# 31_Pwr_In.net
KiCad netlist of a schematic drawn in Altium Designer
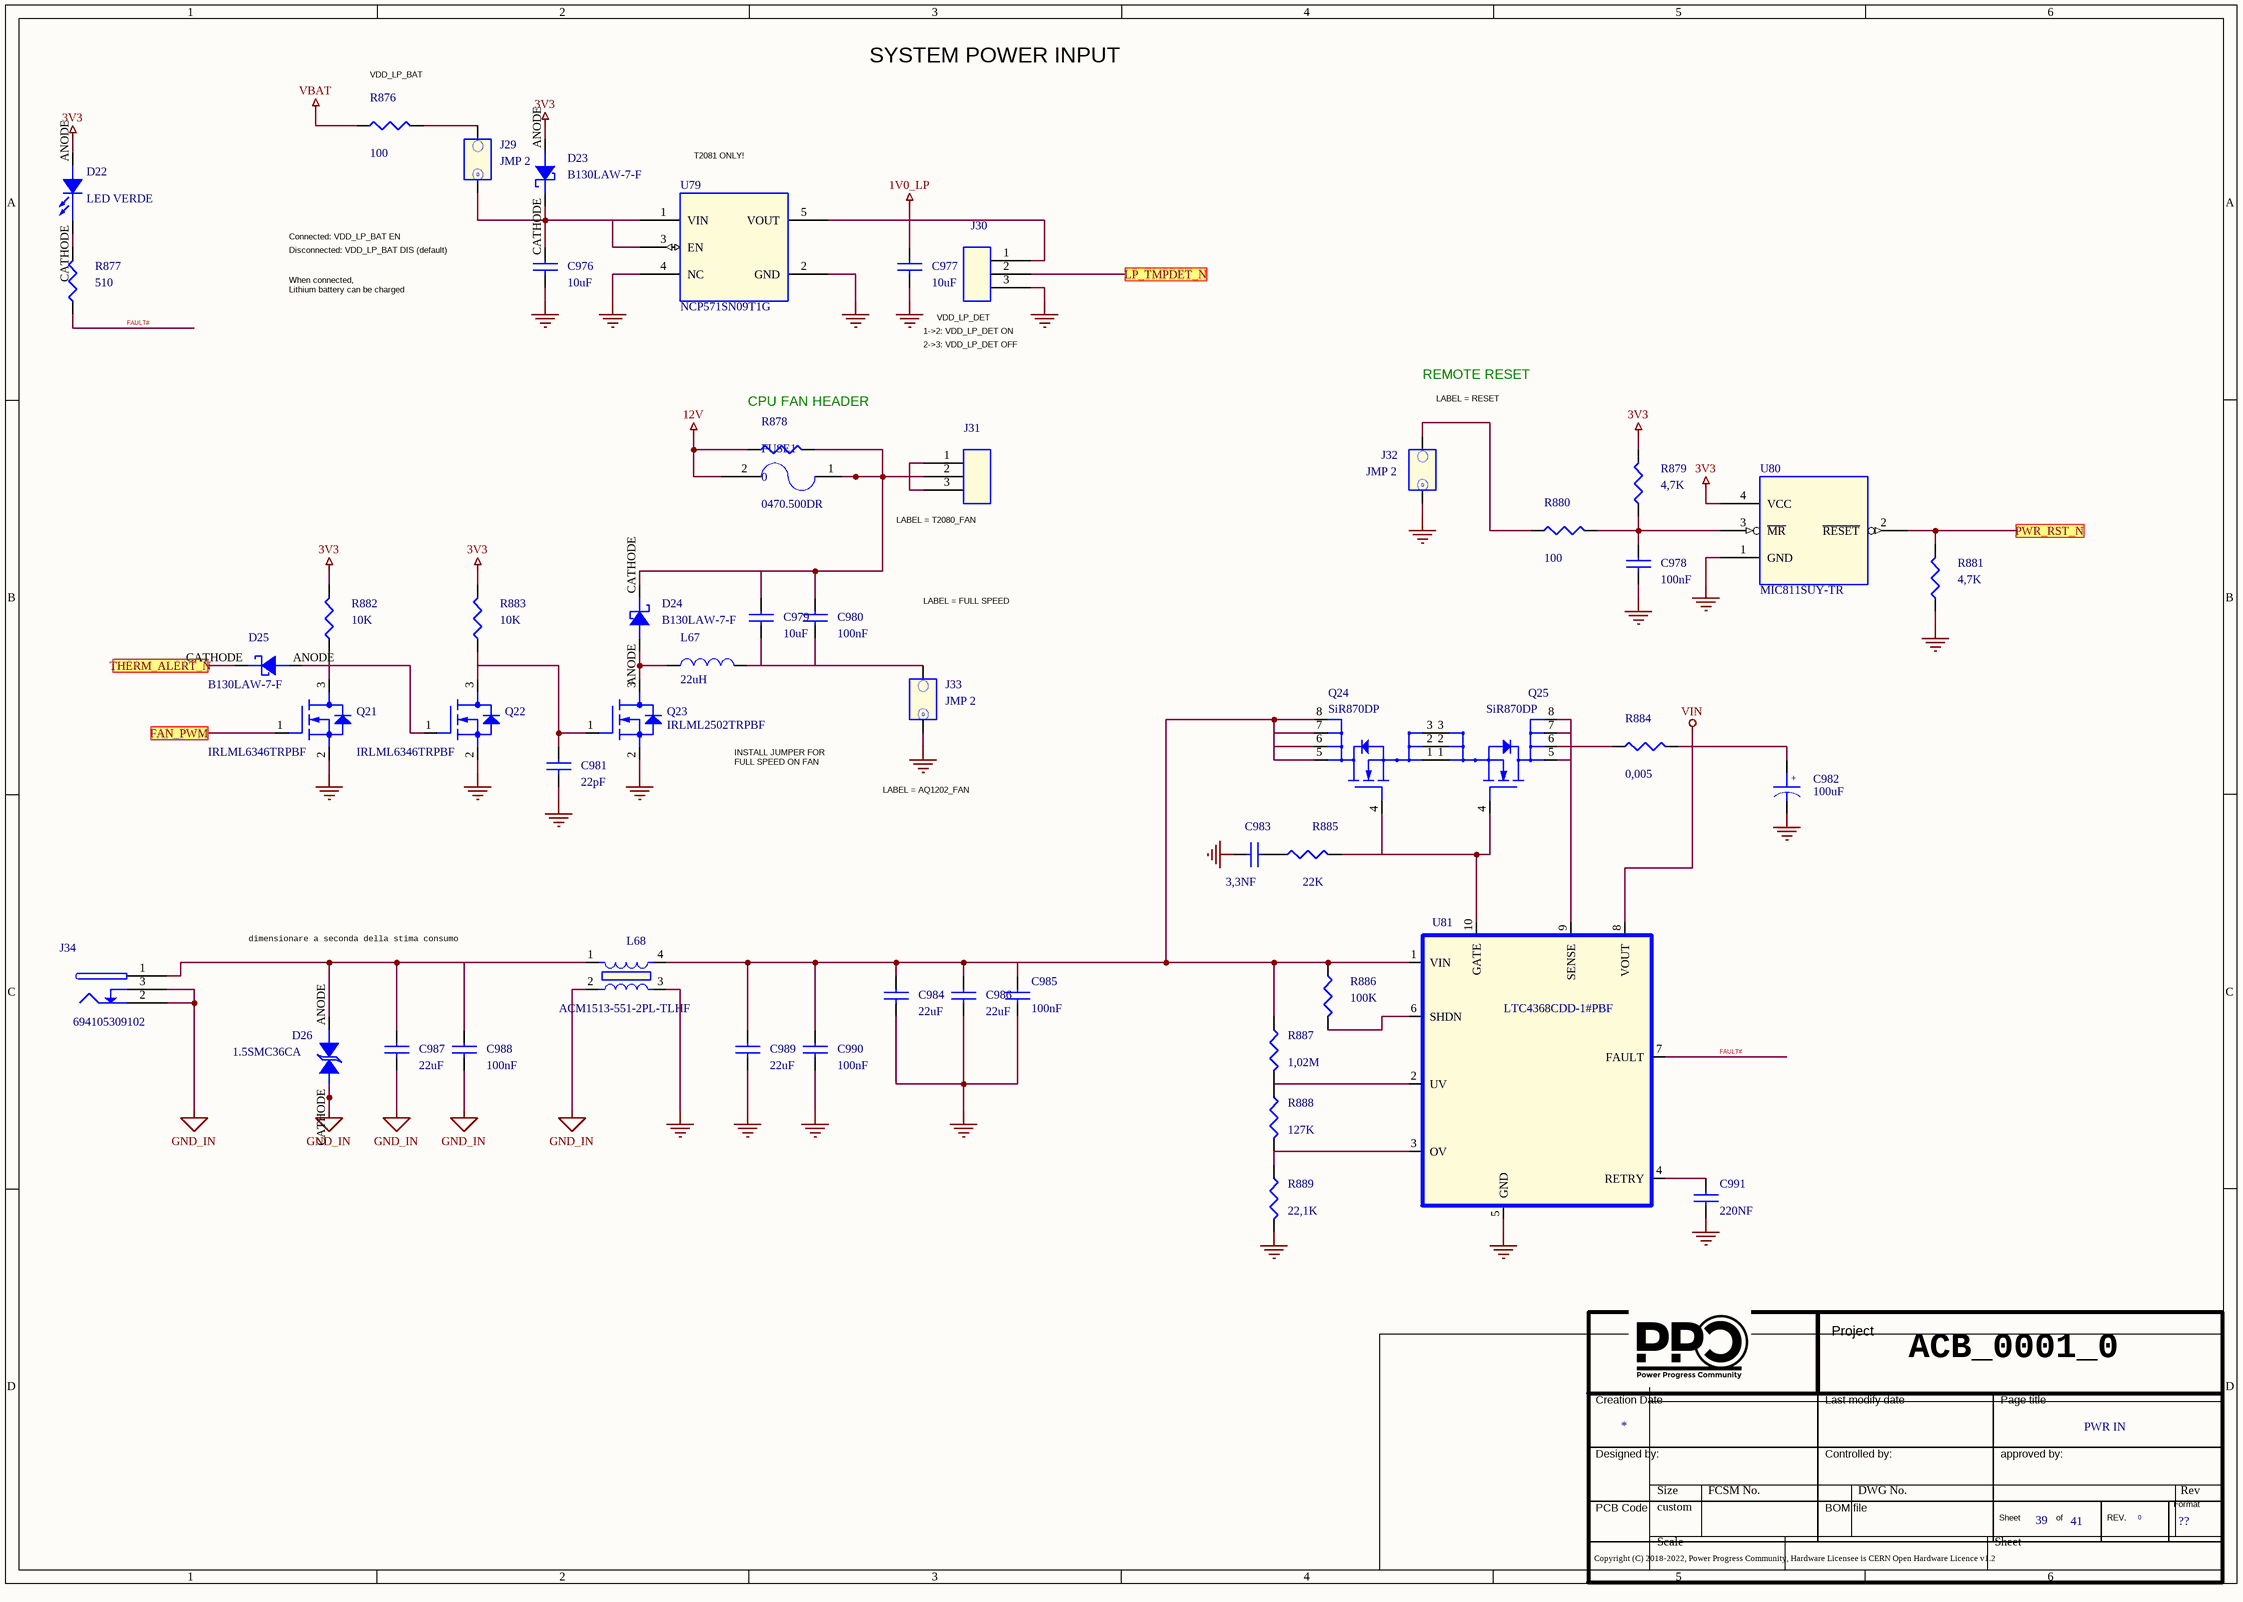
[diagram p0: 31 Pwr In.SchDoc]

(export (version "E")
  (design (tool "Eeschema 10.0.6"))
  (components
    (comp (ref "C976")
      (value "10uF")
      (footprint "SMD_0603")
      (description "COND.CER.10uF 0603 25V SMD")
      (fields (field (name "PART NUMBER") "PASSIVE_124"))
      (libsource (lib "*") (part "CAP NP_Dup3"))
    )
    (comp (ref "C977")
      (value "10uF")
      (footprint "SMD_0603")
      (description "COND.CER.10uF 0603 25V SMD")
      (fields (field (name "PART NUMBER") "PASSIVE_124"))
      (libsource (lib "*") (part "CAP NP_Dup3"))
    )
    (comp (ref "C978")
      (value "100nF")
      (footprint "SMD_0402")
      (description "COND.CER. 100NF 50V 0402 X7R SMD")
      (fields (field (name "PART NUMBER") "PASSIVE_24"))
      (libsource (lib "*") (part "CAP NP_Dup3"))
    )
    (comp (ref "C979")
      (value "10uF")
      (footprint "SMD_0603")
      (description "COND.CER.10uF 0603 25V SMD")
      (fields (field (name "PART NUMBER") "PASSIVE_124"))
      (libsource (lib "*") (part "CAP NP_Dup3"))
    )
    (comp (ref "C980")
      (value "100nF")
      (footprint "SMD_0402")
      (description "COND.CER. 100NF 50V 0402 X7R SMD")
      (fields (field (name "PART NUMBER") "PASSIVE_24"))
      (libsource (lib "*") (part "CAP NP_Dup3"))
    )
    (comp (ref "C981")
      (value "22pF")
      (footprint "SMD_0402")
      (description "COND.CER. 22PF 50V 0402 NPO 5% SMD")
      (fields (field (name "PART NUMBER") "PASSIVE_65"))
      (libsource (lib "*") (part "CAP NP_Dup3"))
    )
    (comp (ref "C982")
      (value "100uF")
      (footprint "SMD_8.3X8.3")
      (description "CAP ALUM 100UF 35V 20% SMD")
      (fields (field (name "PART NUMBER") "PASSIVE_307"))
      (libsource (lib "*") (part "CAP POL_Dup2"))
    )
    (comp (ref "C983")
      (value "3,3NF")
      (footprint "SMD_0402")
      (description "COND.CER. 3,3NF 50V 0402 X7R SMD")
      (fields (field (name "PART NUMBER") "PASSIVE_69"))
      (libsource (lib "*") (part "CAP NP_Dup10"))
    )
    (comp (ref "C984")
      (value "22uF")
      (footprint "SMD_0805")
      (description "22UF 35V 20% 0805")
      (fields (field (name "PART NUMBER") "PASSIVE_224"))
      (libsource (lib "*") (part "CAP NP_Dup3"))
    )
    (comp (ref "C985")
      (value "100nF")
      (footprint "SMD_0603")
      (description "COND.CER.100NF 50V 0603 X7R SMD")
      (fields (field (name "PART NUMBER") "PASSIVE_118"))
      (libsource (lib "*") (part "CAP NP_Dup10"))
    )
    (comp (ref "C986")
      (value "22uF")
      (footprint "SMD_0805")
      (description "22UF 35V 20% 0805")
      (fields (field (name "PART NUMBER") "PASSIVE_224"))
      (libsource (lib "*") (part "CAP NP_Dup3"))
    )
    (comp (ref "C987")
      (value "22uF")
      (footprint "SMD_0805")
      (description "22UF 35V 20% 0805")
      (fields (field (name "PART NUMBER") "PASSIVE_224"))
      (libsource (lib "*") (part "CAP NP_Dup3"))
    )
    (comp (ref "C988")
      (value "100nF")
      (footprint "SMD_0603")
      (description "COND.CER.100NF 50V 0603 X7R SMD")
      (fields (field (name "LNK_PART") "C0603X90") (field (name "PART NUMBER") "PASSIVE_118"))
      (libsource (lib "*") (part "CAP NP_Dup10"))
    )
    (comp (ref "C989")
      (value "22uF")
      (footprint "SMD_0805")
      (description "22UF 35V 20% 0805")
      (fields (field (name "PART NUMBER") "PASSIVE_224"))
      (libsource (lib "*") (part "CAP NP_Dup3"))
    )
    (comp (ref "C990")
      (value "100nF")
      (footprint "SMD_0603")
      (description "COND.CER.100NF 50V 0603 X7R SMD")
      (fields (field (name "LNK_PART") "C0603X90") (field (name "PART NUMBER") "PASSIVE_118"))
      (libsource (lib "*") (part "CAP NP_Dup10"))
    )
    (comp (ref "C991")
      (value "220NF")
      (footprint "SMD_0402")
      (description "COND.CER. 220NF 10V 0402 X5R SMD")
      (fields (field (name "PART NUMBER") "PASSIVE_60"))
      (libsource (lib "*") (part "CAP NP_Dup10"))
    )
    (comp (ref "D22")
      (value "LED VERDE")
      (footprint "led_0603")
      (description "LED CHIPLED VERDE 40mcd 570nm")
      (fields (field (name "PART NUMBER") "DISCRETE_31"))
      (libsource (lib "*") (part "LED_1"))
    )
    (comp (ref "D23")
      (value "B130LAW-7-F")
      (footprint "SOD-123")
      (description "DIODE SCHOTTKY 30V 1A SOD123")
      (fields (field (name "PART NUMBER") "DISCRETE_74"))
      (libsource (lib "*") (part "diode_schottky"))
    )
    (comp (ref "D24")
      (value "B130LAW-7-F")
      (footprint "SOD-123")
      (description "DIODE SCHOTTKY 30V 1A SOD123")
      (fields (field (name "PART NUMBER") "DISCRETE_74"))
      (libsource (lib "*") (part "diode_schottky"))
    )
    (comp (ref "D25")
      (value "B130LAW-7-F")
      (footprint "SOD-123")
      (description "DIODE SCHOTTKY 30V 1A SOD123")
      (fields (field (name "PART NUMBER") "DISCRETE_74"))
      (libsource (lib "*") (part "diode_schottky"))
    )
    (comp (ref "D26")
      (value "1.5SMC36CA")
      (footprint "SMC")
      (description "1.5SMC36A VARISTORE BIDIREZION. 36V SMD")
      (fields (field (name "PART NUMBER") "DISCRETE_207"))
      (libsource (lib "*") (part "BIDIR_TRANSIL_0"))
    )
    (comp (ref "FUSE1")
      (value "0470.500DR")
      (footprint "SMD")
      (description "Surface Mount Fuses SMD FA 0.5A")
      (fields (field (name "PART NUMBER") "MISC_28"))
      (libsource (lib "*") (part "0453008"))
    )
    (comp (ref "J29")
      (value "JMP 2")
      (footprint "PTH")
      (description "STRIP MASC.1x2P P=2.54 H=7.62")
      (fields (field (name "PART NUMBER") "CONNECTORS_445"))
      (libsource (lib "") (part "JUMPER_2_1"))
    )
    (comp (ref "J30")
      (value "B3B-XH-A (LF)(SN)")
      (footprint "3_PIN_PASSO_2.5mm")
      (description "CONN WIRE TO BOARD HEADER. VERTICAL. 3WAY")
      (fields (field (name "PART NUMBER") "CONNECTORS_574"))
      (libsource (lib "") (part "HEADER_3_1"))
    )
    (comp (ref "J31")
      (value "B3B-XH-A (LF)(SN)")
      (footprint "3_PIN_PASSO_2.5mm")
      (description "CONN WIRE TO BOARD HEADER. VERTICAL. 3WAY")
      (fields (field (name "PART NUMBER") "CONNECTORS_574"))
      (libsource (lib "*") (part "HEADER_3"))
    )
    (comp (ref "J32")
      (value "JMP 2")
      (footprint "PTH")
      (description "STRIP MASC.1x2P P=2.54 H=7.62")
      (fields (field (name "PART NUMBER") "CONNECTORS_445"))
      (libsource (lib "*") (part "JUMPER_2"))
    )
    (comp (ref "J33")
      (value "JMP 2")
      (footprint "PTH")
      (description "STRIP MASC.1x2P P=2.54 H=7.62")
      (fields (field (name "PART NUMBER") "CONNECTORS_445"))
      (libsource (lib "") (part "JUMPER_2_1"))
    )
    (comp (ref "J34")
      (value "694105309102")
      (footprint "JACK_PTH")
      (description "CC WR-DC PwrJk CtrPnTHT Right Angled")
      (fields (field (name "PART NUMBER") "CONNECTORS_703"))
      (libsource (lib "*") (part "PWR_JACK"))
    )
    (comp (ref "L67")
      (value "22uH")
      (footprint "SMD_DR73")
      (description "INDUTTANZA 22uH 1,67A DR73-220 SMD")
      (fields (field (name "PART NUMBER") "PASSIVE_502"))
      (libsource (lib "*") (part "INDUCTOR_Dup1"))
    )
    (comp (ref "L68")
      (value "ACM1513-551-2PL-TLHF")
      (footprint "SMD")
      (description "CHOKE COMM MODE 550 OHM 10A SMD")
      (fields (field (name "PART NUMBER") "PASSIVE_356"))
      (libsource (lib "*") (part "CM_CHOKE"))
    )
    (comp (ref "Q21")
      (value "IRLML6346TRPBF")
      (footprint "sot23")
      (description "MOSFET N-CH 30V 3.4A SOT23")
      (fields (field (name "PART NUMBER") "DISCRETE_323"))
      (libsource (lib "*") (part "NMOS"))
    )
    (comp (ref "Q22")
      (value "IRLML6346TRPBF")
      (footprint "sot23")
      (description "MOSFET N-CH 30V 3.4A SOT23")
      (fields (field (name "PART NUMBER") "DISCRETE_323"))
      (libsource (lib "*") (part "NMOS"))
    )
    (comp (ref "Q23")
      (value "IRLML2502TRPBF")
      (footprint "sot23")
      (description "MOSFET N-CH 20V 4.2A SOT-23")
      (fields (field (name "PART NUMBER") "DISCRETE_323"))
      (libsource (lib "*") (part "NMOS"))
    )
    (comp (ref "Q24")
      (value "SiR870DP")
      (footprint "SSOT-6")
      (description "MOSFET 100V 60A 20W 6mohm @ 4.5V")
      (fields (field (name "PART NUMBER") "DISCRETE_281"))
      (libsource (lib "*") (part "MOS_N_SO8_1"))
    )
    (comp (ref "Q25")
      (value "SiR870DP")
      (footprint "SSOT-6")
      (description "MOSFET 100V 60A 20W 6mohm @ 4.5V")
      (fields (field (name "PART NUMBER") "DISCRETE_281"))
      (libsource (lib "*") (part "MOS_N_SO8_1"))
    )
    (comp (ref "R876")
      (value "100")
      (footprint "SMD_0402")
      (description "RESIS.CHIP 100R 5% 0402 SMD")
      (fields (field (name "PART NUMBER") "PASSIVE_812"))
      (libsource (lib "*") (part "R_Dup6"))
    )
    (comp (ref "R877")
      (value "510")
      (footprint "SMD_0402")
      (description "RESIS.CHIP 510R 1% 0402 SMD")
      (fields (field (name "PART NUMBER") "PASSIVE_749"))
      (libsource (lib "*") (part "R_Dup6"))
    )
    (comp (ref "R878")
      (value "0")
      (footprint "SMD_1206")
      (description "RESIS. 0R 1/4W 1206 SMD E96")
      (fields (field (name "PART NUMBER") "PASSIVE_1266"))
      (libsource (lib "*") (part "R_Dup6"))
    )
    (comp (ref "R879")
      (value "4,7K")
      (footprint "SMD_0402")
      (description "RESIS.CHIP 4,7K 5% 0402 SMD")
      (fields (field (name "PART NUMBER") "PASSIVE_861"))
      (libsource (lib "*") (part "R_Dup6"))
    )
    (comp (ref "R880")
      (value "100")
      (footprint "SMD_0402")
      (description "RESIS.CHIP 100R 5% 0402 SMD")
      (fields (field (name "PART NUMBER") "PASSIVE_812"))
      (libsource (lib "*") (part "R_Dup6"))
    )
    (comp (ref "R881")
      (value "4,7K")
      (footprint "SMD_0402")
      (description "RESIS.CHIP 4,7K 5% 0402 SMD")
      (fields (field (name "PART NUMBER") "PASSIVE_861"))
      (libsource (lib "*") (part "R_Dup6"))
    )
    (comp (ref "R882")
      (value "10K")
      (footprint "SMD_0402")
      (description "RESIS.CHIP 10K 1% 0402 SMD")
      (fields (field (name "PART NUMBER") "PASSIVE_584"))
      (libsource (lib "*") (part "R_Dup6"))
    )
    (comp (ref "R883")
      (value "10K")
      (footprint "SMD_0402")
      (description "RESIS.CHIP 10K 1% 0402 SMD")
      (fields (field (name "PART NUMBER") "PASSIVE_584"))
      (libsource (lib "*") (part "R_Dup6"))
    )
    (comp (ref "R884")
      (value "0,005")
      (footprint "SMD_2512")
      (description "RES 0.005 OHM 2W 1% 2512 SMD")
      (fields (field (name "PART NUMBER") "PASSIVE_1376"))
      (libsource (lib "*") (part "R_Dup9"))
    )
    (comp (ref "R885")
      (value "22K")
      (footprint "SMD_0402")
      (description "RESIS.CHIP 22K 5% 0402 SMD")
      (fields (field (name "PART NUMBER") "PASSIVE_843"))
      (libsource (lib "*") (part "R_Dup9"))
    )
    (comp (ref "R886")
      (value "100K")
      (footprint "SMD_0402")
      (description "RESIS.CHIP 100K 5% 0402 SMD")
      (fields (field (name "PART NUMBER") "PASSIVE_813"))
      (libsource (lib "*") (part "R_Dup6"))
    )
    (comp (ref "R887")
      (value "1,02M")
      (footprint "SMD_0402")
      (description "RESIS.CHIP 1,02M 1% 0402 SMD")
      (fields (field (name "PART NUMBER") "PASSIVE_568"))
      (libsource (lib "*") (part "R_Dup9"))
    )
    (comp (ref "R888")
      (value "127K")
      (footprint "SMD_0402")
      (description "RESIS.CHIP 127K 1% 0402 SMD")
      (fields (field (name "PART NUMBER") "PASSIVE_597"))
      (libsource (lib "*") (part "R_Dup9"))
    )
    (comp (ref "R889")
      (value "22,1K")
      (footprint "SMD_0402")
      (description "RESIS.CHIP 22,1K 1% 0402 SMD")
      (fields (field (name "PART NUMBER") "PASSIVE_647"))
      (libsource (lib "*") (part "R_Dup9"))
    )
    (comp (ref "U79")
      (value "NCP571SN09T1G")
      (footprint "SOT-223")
      (description "IC REG LINEAR 0.9V 150MA 5TSOP")
      (fields (field (name "PART NUMBER") "LINEAR_333") (field (name "MPN") "NCP571SN10T1G"))
      (libsource (lib "*") (part "NCP571"))
    )
    (comp (ref "U80")
      (value "MIC811SUY-TR")
      (footprint "SOT143")
      (description "MPU VOLTAGE MONITOR")
      (fields (field (name "PART NUMBER") "LOGIC_362") (field (name "MPN") "MIC811SUY"))
      (libsource (lib "*") (part "MAX811S"))
    )
    (comp (ref "U81")
      (value "LTC4368CDD-1#PBF")
      (footprint "DFN-10PIN-3X3")
      (description "SURGE SUPPRESSIONE ADJ")
      (fields (field (name "PART NUMBER") "LINEAR_286"))
      (libsource (lib "*") (part "LTC4368_0"))
    )
  )
  (nets
    (net (code "1") (name "/FAN_PWM") (class "Default")
      (node (ref "Q21") (pin "1") (pinfunction "G_1") (pintype "passive"))
    )
    (net (code "2") (name "/FAULT#") (class "Default")
      (node (ref "R877") (pin "1") (pinfunction "1_1") (pintype "passive"))
      (node (ref "U81") (pin "7") (pinfunction "FAULT_7") (pintype "passive"))
    )
    (net (code "3") (name "/LP_TMPDET_N") (class "Default")
      (node (ref "J30") (pin "2") (pinfunction "2_2") (pintype "passive"))
    )
    (net (code "4") (name "/PWR_RST_N") (class "Default")
      (node (ref "R881") (pin "2") (pinfunction "2_2") (pintype "passive"))
      (node (ref "U80") (pin "2") (pinfunction "~{RESET}_2") (pintype "output"))
    )
    (net (code "5") (name "/THERM_ALERT_N") (class "Default")
      (node (ref "D25") (pin "CATHODE") (pinfunction "CATHODE_CATHODE") (pintype "passive"))
    )
    (net (code "6") (name "1V0_LP") (class "Default")
      (node (ref "C977") (pin "1") (pinfunction "1_1") (pintype "passive"))
      (node (ref "J30") (pin "1") (pinfunction "1_1") (pintype "passive"))
      (node (ref "U79") (pin "5") (pinfunction "VOUT_5") (pintype "power_in"))
    )
    (net (code "7") (name "3V3") (class "Default")
      (node (ref "D22") (pin "ANODE") (pinfunction "ANODE_ANODE") (pintype "passive"))
      (node (ref "D23") (pin "ANODE") (pinfunction "ANODE_ANODE") (pintype "passive"))
      (node (ref "R879") (pin "2") (pinfunction "2_2") (pintype "passive"))
      (node (ref "R882") (pin "2") (pinfunction "2_2") (pintype "passive"))
      (node (ref "R883") (pin "2") (pinfunction "2_2") (pintype "passive"))
      (node (ref "U80") (pin "4") (pinfunction "VCC_4") (pintype "power_in"))
    )
    (net (code "8") (name "12V") (class "Default")
      (node (ref "FUSE1") (pin "2") (pinfunction "2_2") (pintype "passive"))
      (node (ref "R878") (pin "1") (pinfunction "1_1") (pintype "passive"))
    )
    (net (code "9") (name "GND") (class "Default")
      (node (ref "C976") (pin "2") (pinfunction "2_2") (pintype "passive"))
      (node (ref "C977") (pin "2") (pinfunction "2_2") (pintype "passive"))
      (node (ref "C978") (pin "2") (pinfunction "2_2") (pintype "passive"))
      (node (ref "C981") (pin "2") (pinfunction "2_2") (pintype "passive"))
      (node (ref "C982") (pin "2") (pinfunction "2_2") (pintype "passive"))
      (node (ref "C983") (pin "2") (pinfunction "2_2") (pintype "passive"))
      (node (ref "C984") (pin "2") (pinfunction "2_2") (pintype "passive"))
      (node (ref "C985") (pin "2") (pinfunction "2_2") (pintype "passive"))
      (node (ref "C986") (pin "2") (pinfunction "2_2") (pintype "passive"))
      (node (ref "C989") (pin "2") (pinfunction "2_2") (pintype "passive"))
      (node (ref "C990") (pin "2") (pinfunction "2_2") (pintype "passive"))
      (node (ref "C991") (pin "2") (pinfunction "2_2") (pintype "passive"))
      (node (ref "J30") (pin "3") (pinfunction "3_3") (pintype "passive"))
      (node (ref "J32") (pin "1") (pinfunction "1_1") (pintype "passive"))
      (node (ref "J33") (pin "1") (pinfunction "1_1") (pintype "passive"))
      (node (ref "L68") (pin "3") (pinfunction "3_3") (pintype "passive"))
      (node (ref "Q21") (pin "2") (pinfunction "S_2") (pintype "passive"))
      (node (ref "Q22") (pin "2") (pinfunction "S_2") (pintype "passive"))
      (node (ref "Q23") (pin "2") (pinfunction "S_2") (pintype "passive"))
      (node (ref "R881") (pin "1") (pinfunction "1_1") (pintype "passive"))
      (node (ref "R889") (pin "2") (pinfunction "2_2") (pintype "passive"))
      (node (ref "U79") (pin "2") (pinfunction "GND_2") (pintype "power_in"))
      (node (ref "U79") (pin "4") (pinfunction "NC_4") (pintype "passive"))
      (node (ref "U80") (pin "1") (pinfunction "GND_1") (pintype "power_in"))
      (node (ref "U81") (pin "5") (pinfunction "GND_5") (pintype "passive"))
    )
    (net (code "10") (name "GND_IN") (class "Default")
      (node (ref "C987") (pin "2") (pinfunction "2_2") (pintype "passive"))
      (node (ref "C988") (pin "2") (pinfunction "2_2") (pintype "passive"))
      (node (ref "D26") (pin "CATHODE") (pinfunction "CATHODE_CATHODE") (pintype "passive"))
      (node (ref "J34") (pin "2") (pinfunction "2_2") (pintype "passive"))
      (node (ref "J34") (pin "3") (pinfunction "3_3") (pintype "passive"))
      (node (ref "L68") (pin "2") (pinfunction "2_2") (pintype "passive"))
    )
    (net (code "11") (name "Net-(C979-Pad1)") (class "Default")
      (node (ref "C979") (pin "1") (pinfunction "1_1") (pintype "passive"))
      (node (ref "C980") (pin "1") (pinfunction "1_1") (pintype "passive"))
      (node (ref "D24") (pin "CATHODE") (pinfunction "CATHODE_CATHODE") (pintype "passive"))
      (node (ref "FUSE1") (pin "1") (pinfunction "1_1") (pintype "passive"))
      (node (ref "J31") (pin "2") (pinfunction "2_2") (pintype "passive"))
      (node (ref "R878") (pin "2") (pinfunction "2_2") (pintype "passive"))
    )
    (net (code "12") (name "Net-(C979-Pad2)") (class "Default")
      (node (ref "C979") (pin "2") (pinfunction "2_2") (pintype "passive"))
      (node (ref "C980") (pin "2") (pinfunction "2_2") (pintype "passive"))
      (node (ref "J33") (pin "2") (pinfunction "2_2") (pintype "passive"))
      (node (ref "L67") (pin "2") (pinfunction "2_2") (pintype "passive"))
    )
    (net (code "13") (name "Net-(C983-Pad1)") (class "Default")
      (node (ref "C983") (pin "1") (pinfunction "1_1") (pintype "passive"))
      (node (ref "R885") (pin "2") (pinfunction "2_2") (pintype "passive"))
    )
    (net (code "14") (name "Net-(C987-Pad1)") (class "Default")
      (node (ref "C987") (pin "1") (pinfunction "1_1") (pintype "passive"))
      (node (ref "C988") (pin "1") (pinfunction "1_1") (pintype "passive"))
      (node (ref "D26") (pin "ANODE") (pinfunction "ANODE_ANODE") (pintype "passive"))
      (node (ref "J34") (pin "1") (pinfunction "1_1") (pintype "passive"))
      (node (ref "L68") (pin "1") (pinfunction "1_1") (pintype "passive"))
    )
    (net (code "15") (name "Net-(D22-PadCATHODE)") (class "Default")
      (node (ref "D22") (pin "CATHODE") (pinfunction "CATHODE_CATHODE") (pintype "passive"))
      (node (ref "R877") (pin "2") (pinfunction "2_2") (pintype "passive"))
    )
    (net (code "16") (name "Net-(J29-Pad2)") (class "Default")
      (node (ref "J29") (pin "2") (pinfunction "2_2") (pintype "passive"))
      (node (ref "R876") (pin "2") (pinfunction "2_2") (pintype "passive"))
    )
    (net (code "17") (name "Net-(J31-Pad1)") (class "Default")
      (node (ref "J31") (pin "1") (pinfunction "1_1") (pintype "passive"))
      (node (ref "J31") (pin "3") (pinfunction "3_3") (pintype "passive"))
    )
    (net (code "18") (name "Net-(J32-Pad2)") (class "Default")
      (node (ref "J32") (pin "2") (pinfunction "2_2") (pintype "passive"))
      (node (ref "R880") (pin "1") (pinfunction "1_1") (pintype "passive"))
    )
    (net (code "19") (name "Net-(Q21-D)") (class "Default")
      (node (ref "D25") (pin "ANODE") (pinfunction "ANODE_ANODE") (pintype "passive"))
      (node (ref "Q21") (pin "3") (pinfunction "D_3") (pintype "passive"))
      (node (ref "Q22") (pin "1") (pinfunction "G_1") (pintype "passive"))
      (node (ref "R882") (pin "1") (pinfunction "1_1") (pintype "passive"))
    )
    (net (code "20") (name "Net-(Q22-D)") (class "Default")
      (node (ref "C981") (pin "1") (pinfunction "1_1") (pintype "passive"))
      (node (ref "Q22") (pin "3") (pinfunction "D_3") (pintype "passive"))
      (node (ref "Q23") (pin "1") (pinfunction "G_1") (pintype "passive"))
      (node (ref "R883") (pin "1") (pinfunction "1_1") (pintype "passive"))
    )
    (net (code "21") (name "Net-(Q23-D)") (class "Default")
      (node (ref "D24") (pin "ANODE") (pinfunction "ANODE_ANODE") (pintype "passive"))
      (node (ref "L67") (pin "1") (pinfunction "1_1") (pintype "passive"))
      (node (ref "Q23") (pin "3") (pinfunction "D_3") (pintype "passive"))
    )
    (net (code "22") (name "Net-(Q24-D1)") (class "Default")
      (node (ref "C984") (pin "1") (pinfunction "1_1") (pintype "passive"))
      (node (ref "C985") (pin "1") (pinfunction "1_1") (pintype "passive"))
      (node (ref "C986") (pin "1") (pinfunction "1_1") (pintype "passive"))
      (node (ref "C989") (pin "1") (pinfunction "1_1") (pintype "passive"))
      (node (ref "C990") (pin "1") (pinfunction "1_1") (pintype "passive"))
      (node (ref "L68") (pin "4") (pinfunction "4_4") (pintype "passive"))
      (node (ref "Q24") (pin "5") (pinfunction "D1_5") (pintype "passive"))
      (node (ref "Q24") (pin "6") (pinfunction "6_6") (pintype "passive"))
      (node (ref "Q24") (pin "7") (pinfunction "7_7") (pintype "passive"))
      (node (ref "Q24") (pin "8") (pinfunction "8_8") (pintype "passive"))
      (node (ref "R886") (pin "1") (pinfunction "1_1") (pintype "passive"))
      (node (ref "R887") (pin "1") (pinfunction "1_1") (pintype "passive"))
      (node (ref "U81") (pin "1") (pinfunction "VIN_1") (pintype "passive"))
    )
    (net (code "23") (name "Net-(Q24-G)") (class "Default")
      (node (ref "Q24") (pin "4") (pinfunction "G_4") (pintype "passive"))
      (node (ref "Q25") (pin "4") (pinfunction "G_4") (pintype "passive"))
      (node (ref "R885") (pin "1") (pinfunction "1_1") (pintype "passive"))
      (node (ref "U81") (pin "10") (pinfunction "GATE_10") (pintype "passive"))
    )
    (net (code "24") (name "Net-(Q24-S1)") (class "Default")
      (node (ref "Q24") (pin "1") (pinfunction "S1_1") (pintype "passive"))
      (node (ref "Q25") (pin "1") (pinfunction "S1_1") (pintype "passive"))
    )
    (net (code "25") (name "Net-(Q24-S2)") (class "Default")
      (node (ref "Q24") (pin "2") (pinfunction "S2_2") (pintype "passive"))
      (node (ref "Q25") (pin "2") (pinfunction "S2_2") (pintype "passive"))
    )
    (net (code "26") (name "Net-(Q24-S3)") (class "Default")
      (node (ref "Q24") (pin "3") (pinfunction "S3_3") (pintype "passive"))
      (node (ref "Q25") (pin "3") (pinfunction "S3_3") (pintype "passive"))
    )
    (net (code "27") (name "Net-(Q25-D1)") (class "Default")
      (node (ref "Q25") (pin "5") (pinfunction "D1_5") (pintype "passive"))
      (node (ref "Q25") (pin "6") (pinfunction "6_6") (pintype "passive"))
      (node (ref "Q25") (pin "7") (pinfunction "7_7") (pintype "passive"))
      (node (ref "Q25") (pin "8") (pinfunction "8_8") (pintype "passive"))
      (node (ref "R884") (pin "1") (pinfunction "1_1") (pintype "passive"))
      (node (ref "U81") (pin "9") (pinfunction "SENSE_9") (pintype "passive"))
    )
    (net (code "28") (name "Net-(U79-EN)") (class "Default")
      (node (ref "C976") (pin "1") (pinfunction "1_1") (pintype "passive"))
      (node (ref "D23") (pin "CATHODE") (pinfunction "CATHODE_CATHODE") (pintype "passive"))
      (node (ref "J29") (pin "1") (pinfunction "1_1") (pintype "passive"))
      (node (ref "U79") (pin "1") (pinfunction "VIN_1") (pintype "power_in"))
      (node (ref "U79") (pin "3") (pinfunction "EN_3") (pintype "bidirectional"))
    )
    (net (code "29") (name "Net-(U80-~{MR})") (class "Default")
      (node (ref "C978") (pin "1") (pinfunction "1_1") (pintype "passive"))
      (node (ref "R879") (pin "1") (pinfunction "1_1") (pintype "passive"))
      (node (ref "R880") (pin "2") (pinfunction "2_2") (pintype "passive"))
      (node (ref "U80") (pin "3") (pinfunction "~{MR}_3") (pintype "input"))
    )
    (net (code "30") (name "Net-(U81-OV)") (class "Default")
      (node (ref "R888") (pin "2") (pinfunction "2_2") (pintype "passive"))
      (node (ref "R889") (pin "1") (pinfunction "1_1") (pintype "passive"))
      (node (ref "U81") (pin "3") (pinfunction "OV_3") (pintype "passive"))
    )
    (net (code "31") (name "Net-(U81-RETRY)") (class "Default")
      (node (ref "C991") (pin "1") (pinfunction "1_1") (pintype "passive"))
      (node (ref "U81") (pin "4") (pinfunction "RETRY_4") (pintype "passive"))
    )
    (net (code "32") (name "Net-(U81-SHDN)") (class "Default")
      (node (ref "R886") (pin "2") (pinfunction "2_2") (pintype "passive"))
      (node (ref "U81") (pin "6") (pinfunction "SHDN_6") (pintype "passive"))
    )
    (net (code "33") (name "Net-(U81-UV)") (class "Default")
      (node (ref "R887") (pin "2") (pinfunction "2_2") (pintype "passive"))
      (node (ref "R888") (pin "1") (pinfunction "1_1") (pintype "passive"))
      (node (ref "U81") (pin "2") (pinfunction "UV_2") (pintype "passive"))
    )
    (net (code "34") (name "VBAT") (class "Default")
      (node (ref "R876") (pin "1") (pinfunction "1_1") (pintype "passive"))
    )
    (net (code "35") (name "VIN") (class "Default")
      (node (ref "C982") (pin "1") (pinfunction "1_1") (pintype "passive"))
      (node (ref "R884") (pin "2") (pinfunction "2_2") (pintype "passive"))
      (node (ref "U81") (pin "8") (pinfunction "VOUT_8") (pintype "passive"))
    )
  )
)
